# USB_SPI_I2C.net
KiCad netlist of a schematic drawn in Altium Designer
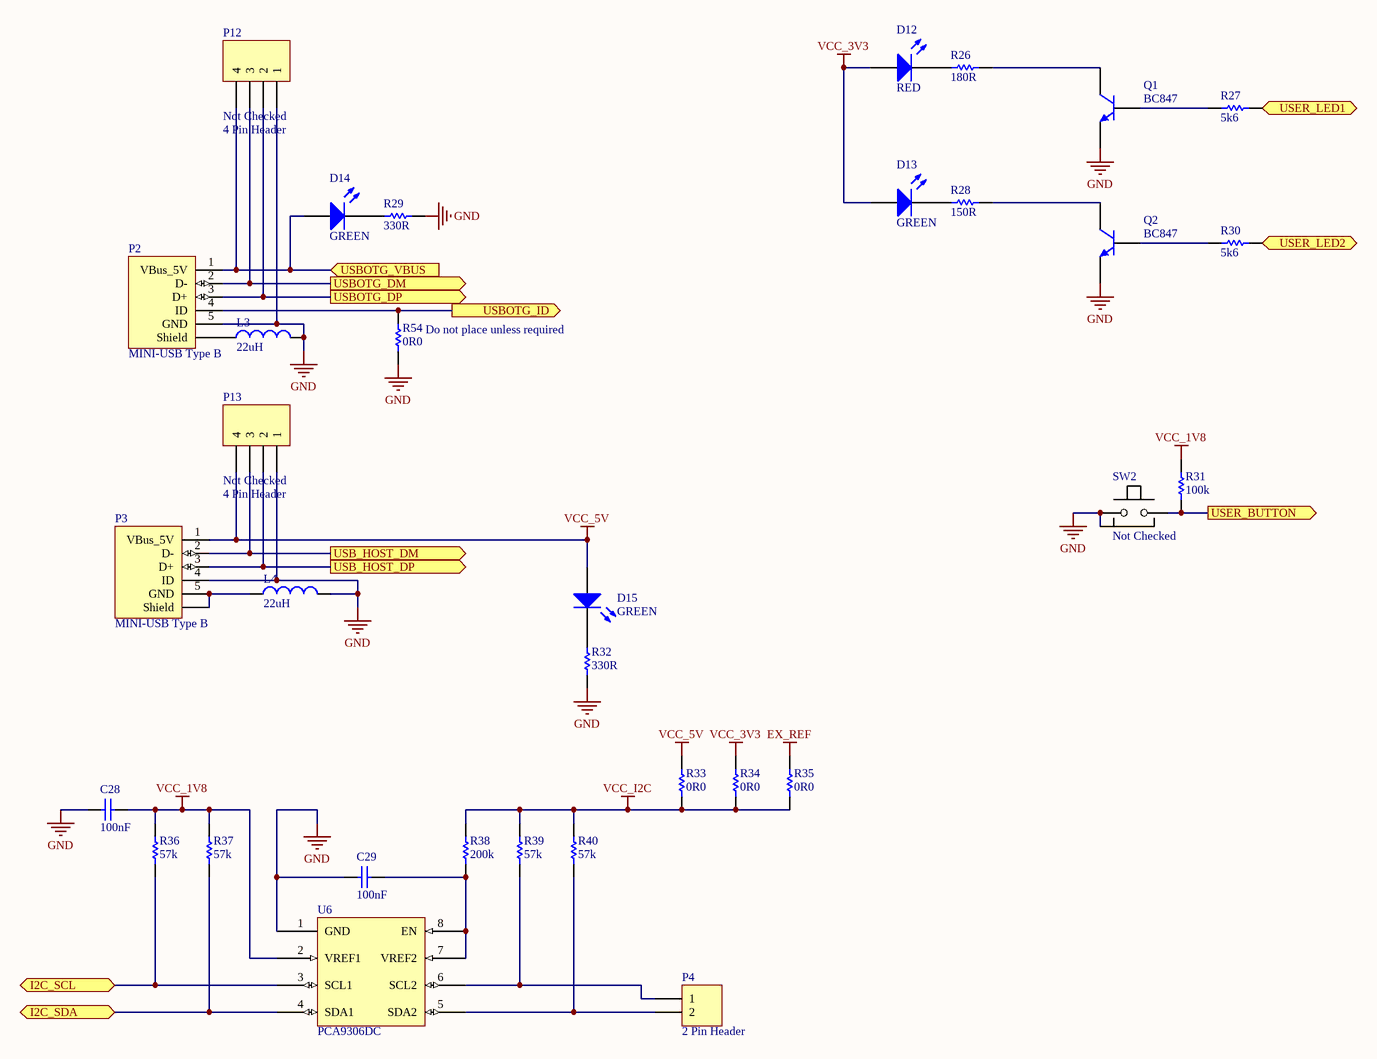
[diagram p0: USB SPI I2C.SchDoc]

(export (version "E")
  (design (tool "Eeschema 10.0.6"))
  (components
    (comp (ref "C28")
      (value "100nF")
      (footprint "GRC PCB library:0603")
      (description "CAP CER .10UF 50V X5R 0603")
      (fields (field (name "MANUFACTURER") "Taiyo Yuden"))
      (libsource (lib "GRC sch library") (part "CP_100nF 0603"))
    )
    (comp (ref "C29")
      (value "100nF")
      (footprint "GRC PCB library:0603")
      (description "CAP CER .10UF 50V X5R 0603")
      (fields (field (name "MANUFACTURER") "Taiyo Yuden"))
      (libsource (lib "GRC sch library") (part "CP_100nF 0603"))
    )
    (comp (ref "D12")
      (value "RED")
      (footprint "Diode_0805")
      (description "Red LED 0805")
      (fields (field (name "MANUFACTURER") "Vishay") (field (name "Comment") "LED Red"))
      (libsource (lib "GRC sch library") (part "DL_LED Red 0805"))
    )
    (comp (ref "D13")
      (value "GREEN")
      (footprint "Diode_0805")
      (description "Green LED 0805")
      (fields (field (name "Comment") "LED Green"))
      (libsource (lib "GRC sch library") (part "DL_LED Green 0805"))
    )
    (comp (ref "D14")
      (value "GREEN")
      (footprint "Diode_0805")
      (description "Green LED 0805")
      (fields (field (name "Comment") "LED Green"))
      (libsource (lib "GRC sch library") (part "DL_LED Green 0805"))
    )
    (comp (ref "D15")
      (value "GREEN")
      (footprint "Diode_0805")
      (description "Green LED 0805")
      (fields (field (name "Comment") "LED Green"))
      (libsource (lib "GRC sch library") (part "DL_LED Green 0805"))
    )
    (comp (ref "L3")
      (value "22uH")
      (footprint "GRC PCB library:0805")
      (description "Inductor 22uH 100mA 10% 0805")
      (fields (field (name "MANUFACTURER") "TDK Corporation"))
      (libsource (lib "GRC sch library") (part "IN_22uH 100mA 0805"))
    )
    (comp (ref "L4")
      (value "22uH")
      (footprint "GRC PCB library:0805")
      (description "Inductor 22uH 100mA 10% 0805")
      (fields (field (name "MANUFACTURER") "TDK Corporation"))
      (libsource (lib "GRC sch library") (part "IN_22uH 100mA 0805"))
    )
    (comp (ref "P2")
      (value "MINI-USB Type B")
      (footprint "Hir_MINI_USB_B")
      (description "MINI-USB Type B Single Connector")
      (fields (field (name "MANUFACTURER") "Hirose Electric Co Ltd"))
      (libsource (lib "GRC sch library") (part "JP_MINIUSB type B_1"))
    )
    (comp (ref "P3")
      (value "MINI-USB Type B")
      (footprint "Hir_MINI_USB_B")
      (description "MINI-USB Type B Single Connector")
      (fields (field (name "MANUFACTURER") "Hirose Electric Co Ltd"))
      (libsource (lib "GRC sch library") (part "JP_MINIUSB type B_1"))
    )
    (comp (ref "P4")
      (value "2 Pin Header")
      (footprint "CONN_2X1_SMT_RA_1.25MM")
      (description "CONN HDR VERT 2POS .100\" SNGL")
      (libsource (lib "checked") (part "JP_2PIN HDR_SMT_RA_MOLEX"))
    )
    (comp (ref "P12")
      (value "4 Pin Header")
      (footprint "CONN_4X1_SMT_RA_1.25MM")
      (description "CONN HDR VERT 4POS .100\" SNGL")
      (fields (field (name "MANUFACTURER") "Molex") (field (name "VERIFY") "Not Checked"))
      (libsource (lib "checked") (part "JP_4PIN HDR_SMT_RA_MOLEX"))
    )
    (comp (ref "P13")
      (value "4 Pin Header")
      (footprint "CONN_4X1_SMT_RA_1.25MM")
      (description "CONN HDR VERT 4POS .100\" SNGL")
      (fields (field (name "MANUFACTURER") "Molex") (field (name "VERIFY") "Not Checked"))
      (libsource (lib "checked") (part "JP_4PIN HDR_SMT_RA_MOLEX"))
    )
    (comp (ref "Q1")
      (value "BC847")
      (footprint "GRC PCB library:SOT23")
      (description "TRANS NPN GP 100MA 45V SOT23")
      (fields (field (name "MANUFACTURER") "NXP Semiconductors"))
      (libsource (lib "GRC sch library") (part "TN_BC847"))
    )
    (comp (ref "Q2")
      (value "BC847")
      (footprint "GRC PCB library:SOT23")
      (description "TRANS NPN GP 100MA 45V SOT23")
      (fields (field (name "MANUFACTURER") "NXP Semiconductors"))
      (libsource (lib "GRC sch library") (part "TN_BC847"))
    )
    (comp (ref "R26")
      (value "180R")
      (footprint "GRC PCB library:0603")
      (description "RES 180OHM 1/10W 1% 0603 SMD")
      (fields (field (name "MANUFACTURER") "Panasonic - ECG"))
      (libsource (lib "GRC sch library") (part "RS_180R 0603"))
    )
    (comp (ref "R27")
      (value "5k6")
      (footprint "GRC PCB library:0603")
      (description "RES 5.6K OHM 1/10W 5% 0603 SMD")
      (fields (field (name "MANUFACTURER") "Yageo"))
      (libsource (lib "GRC sch library") (part "RS_5k6 0603"))
    )
    (comp (ref "R28")
      (value "150R")
      (footprint "GRC PCB library:0603")
      (description "RES 150 OHM 1/10W 1% 0603 SMD")
      (fields (field (name "MANUFACTURER") "ROHM"))
      (libsource (lib "GRC sch library") (part "RS_150R 0603"))
    )
    (comp (ref "R29")
      (value "330R")
      (footprint "GRC PCB library:0603")
      (description "RES 330 OHM 1/10W 1% 0603 SMD")
      (fields (field (name "MANUFACTURER") "Yageo"))
      (libsource (lib "GRC sch library") (part "RS_330R 0603"))
    )
    (comp (ref "R30")
      (value "5k6")
      (footprint "GRC PCB library:0603")
      (description "RES 5.6K OHM 1/10W 5% 0603 SMD")
      (fields (field (name "MANUFACTURER") "Yageo"))
      (libsource (lib "GRC sch library") (part "RS_5k6 0603"))
    )
    (comp (ref "R31")
      (value "100k")
      (footprint "GRC PCB library:0603")
      (description "RES 100K OHM 1/10W 1% 0603 SMD")
      (fields (field (name "MANUFACTURER") "Yageo"))
      (libsource (lib "GRC sch library") (part "RS_100k 0603"))
    )
    (comp (ref "R32")
      (value "330R")
      (footprint "GRC PCB library:0603")
      (description "RES 100K OHM 1/10W 1% 0603 SMD")
      (fields (field (name "MANUFACTURER") "Yageo"))
      (libsource (lib "GRC sch library") (part "RS_100k 0603"))
    )
    (comp (ref "R33")
      (value "0R0")
      (footprint "GRC PCB library:0603")
      (description "RES 0.0 OHM 1/10W 5% 0603 SMD")
      (fields (field (name "MANUFACTURER") "Rohm"))
      (libsource (lib "GRC sch library") (part "RS_0R0 0603"))
    )
    (comp (ref "R34")
      (value "0R0")
      (footprint "GRC PCB library:0603")
      (description "RES 0.0 OHM 1/10W 5% 0603 SMD")
      (fields (field (name "MANUFACTURER") "Rohm"))
      (libsource (lib "GRC sch library") (part "RS_0R0 0603"))
    )
    (comp (ref "R35")
      (value "0R0")
      (footprint "GRC PCB library:0603")
      (description "RES 0.0 OHM 1/10W 5% 0603 SMD")
      (fields (field (name "MANUFACTURER") "Rohm"))
      (libsource (lib "GRC sch library") (part "RS_0R0 0603"))
    )
    (comp (ref "R36")
      (value "57k")
      (footprint "GRC PCB library:0603")
      (description "RES 10.0K OHM 1/10W 1% 0603 SMD")
      (fields (field (name "MANUFACTURER") "Yageo"))
      (libsource (lib "GRC sch library") (part "RS_10k 0603_1"))
    )
    (comp (ref "R37")
      (value "57k")
      (footprint "GRC PCB library:0603")
      (description "RES 10.0K OHM 1/10W 1% 0603 SMD")
      (fields (field (name "MANUFACTURER") "Yageo"))
      (libsource (lib "GRC sch library") (part "RS_10k 0603_1"))
    )
    (comp (ref "R38")
      (value "200k")
      (footprint "GRC PCB library:0603")
      (description "RES 10.0K OHM 1/10W 1% 0603 SMD")
      (fields (field (name "MANUFACTURER") "Yageo"))
      (libsource (lib "GRC sch library") (part "RS_10k 0603_1"))
    )
    (comp (ref "R39")
      (value "57k")
      (footprint "GRC PCB library:0603")
      (description "RES 10.0K OHM 1/10W 1% 0603 SMD")
      (fields (field (name "MANUFACTURER") "Yageo"))
      (libsource (lib "GRC sch library") (part "RS_10k 0603_1"))
    )
    (comp (ref "R40")
      (value "57k")
      (footprint "GRC PCB library:0603")
      (description "RES 10.0K OHM 1/10W 1% 0603 SMD")
      (fields (field (name "MANUFACTURER") "Yageo"))
      (libsource (lib "GRC sch library") (part "RS_10k 0603_1"))
    )
    (comp (ref "R54")
      (value "0R0")
      (footprint "GRC PCB library:0603")
      (description "RES 0.0 OHM 1/10W 5% 0603 SMD")
      (fields (field (name "MANUFACTURER") "Rohm"))
      (libsource (lib "GRC sch library") (part "RS_0R0 0603"))
    )
    (comp (ref "SW2")
      (value "Push Button Switch")
      (footprint "PUSHBUTTON_B3U")
      (description "SWITCH TACT RT ANG SPST SMD")
      (fields (field (name "MANUFACTURER") "Omron") (field (name "VERIFY") "Not Checked"))
      (libsource (lib "GRC sch library") (part "SW_TACT 3MM RT"))
    )
    (comp (ref "U6")
      (value "PCA9306DC")
      (footprint "VSSOP-8")
      (description "IC LEVEL TRANSLATOR I2C BUS 8VSSOP")
      (fields (field (name "MANUFACTURER") "NXP Semiconductor"))
      (libsource (lib "GRC sch library") (part "IC_PCA9306DC"))
    )
  )
  (nets
    (net (code "1") (name "/I2C_SCL") (class "Default")
      (node (ref "R36") (pin "1") (pinfunction "1_1") (pintype "passive"))
      (node (ref "U6") (pin "3") (pinfunction "SCL1_3") (pintype "bidirectional"))
    )
    (net (code "2") (name "/I2C_SDA") (class "Default")
      (node (ref "R37") (pin "1") (pinfunction "1_1") (pintype "passive"))
      (node (ref "U6") (pin "4") (pinfunction "SDA1_4") (pintype "bidirectional"))
    )
    (net (code "3") (name "/USBOTG_DM") (class "Default")
      (node (ref "P12") (pin "3") (pinfunction "3_3") (pintype "passive"))
      (node (ref "P2") (pin "2") (pinfunction "D-_2") (pintype "bidirectional"))
    )
    (net (code "4") (name "/USBOTG_DP") (class "Default")
      (node (ref "P12") (pin "2") (pinfunction "2_2") (pintype "passive"))
      (node (ref "P2") (pin "3") (pinfunction "D+_3") (pintype "bidirectional"))
    )
    (net (code "5") (name "/USBOTG_ID") (class "Default")
      (node (ref "P2") (pin "4") (pinfunction "ID_4") (pintype "passive"))
      (node (ref "R54") (pin "1") (pinfunction "1_1") (pintype "passive"))
    )
    (net (code "6") (name "/USBOTG_VBUS") (class "Default")
      (node (ref "D14") (pin "1") (pinfunction "A_1") (pintype "passive"))
      (node (ref "P12") (pin "4") (pinfunction "4_4") (pintype "passive"))
      (node (ref "P2") (pin "1") (pinfunction "VBus_5V_1") (pintype "passive"))
    )
    (net (code "7") (name "/USB_HOST_DM") (class "Default")
      (node (ref "P13") (pin "3") (pinfunction "3_3") (pintype "passive"))
      (node (ref "P3") (pin "2") (pinfunction "D-_2") (pintype "bidirectional"))
    )
    (net (code "8") (name "/USB_HOST_DP") (class "Default")
      (node (ref "P13") (pin "2") (pinfunction "2_2") (pintype "passive"))
      (node (ref "P3") (pin "3") (pinfunction "D+_3") (pintype "bidirectional"))
    )
    (net (code "9") (name "/USER_BUTTON") (class "Default")
      (node (ref "R31") (pin "2") (pinfunction "2_2") (pintype "passive"))
      (node (ref "SW2") (pin "2") (pinfunction "2_2") (pintype "passive"))
    )
    (net (code "10") (name "/USER_LED1") (class "Default")
      (node (ref "R27") (pin "2") (pinfunction "2_2") (pintype "passive"))
    )
    (net (code "11") (name "/USER_LED2") (class "Default")
      (node (ref "R30") (pin "2") (pinfunction "2_2") (pintype "passive"))
    )
    (net (code "12") (name "EX_REF") (class "Default")
      (node (ref "R35") (pin "1") (pinfunction "1_1") (pintype "passive"))
    )
    (net (code "13") (name "GND") (class "Default")
      (node (ref "C28") (pin "2") (pinfunction "2_2") (pintype "passive"))
      (node (ref "C29") (pin "2") (pinfunction "2_2") (pintype "passive"))
      (node (ref "L3") (pin "2") (pinfunction "2_2") (pintype "passive"))
      (node (ref "L4") (pin "2") (pinfunction "2_2") (pintype "passive"))
      (node (ref "P12") (pin "1") (pinfunction "1_1") (pintype "passive"))
      (node (ref "P13") (pin "1") (pinfunction "1_1") (pintype "passive"))
      (node (ref "P2") (pin "5") (pinfunction "GND_5") (pintype "passive"))
      (node (ref "P3") (pin "4") (pinfunction "ID_4") (pintype "passive"))
      (node (ref "Q1") (pin "2") (pinfunction "E_2") (pintype "passive"))
      (node (ref "Q2") (pin "2") (pinfunction "E_2") (pintype "passive"))
      (node (ref "R29") (pin "2") (pinfunction "2_2") (pintype "passive"))
      (node (ref "R32") (pin "1") (pinfunction "1_1") (pintype "passive"))
      (node (ref "R54") (pin "2") (pinfunction "2_2") (pintype "passive"))
      (node (ref "SW2") (pin "1") (pinfunction "1_1") (pintype "passive"))
      (node (ref "SW2") (pin "3") (pinfunction "GND_3") (pintype "passive"))
      (node (ref "U6") (pin "1") (pinfunction "GND_1") (pintype "power_in"))
    )
    (net (code "14") (name "Net-(D12-K)") (class "Default")
      (node (ref "D12") (pin "2") (pinfunction "K_2") (pintype "passive"))
      (node (ref "R26") (pin "1") (pinfunction "1_1") (pintype "passive"))
    )
    (net (code "15") (name "Net-(D13-K)") (class "Default")
      (node (ref "D13") (pin "2") (pinfunction "K_2") (pintype "passive"))
      (node (ref "R28") (pin "1") (pinfunction "1_1") (pintype "passive"))
    )
    (net (code "16") (name "Net-(D14-K)") (class "Default")
      (node (ref "D14") (pin "2") (pinfunction "K_2") (pintype "passive"))
      (node (ref "R29") (pin "1") (pinfunction "1_1") (pintype "passive"))
    )
    (net (code "17") (name "Net-(D15-K)") (class "Default")
      (node (ref "D15") (pin "2") (pinfunction "K_2") (pintype "passive"))
      (node (ref "R32") (pin "2") (pinfunction "2_2") (pintype "passive"))
    )
    (net (code "18") (name "Net-(P2-Shield)") (class "Default")
      (node (ref "L3") (pin "1") (pinfunction "1_1") (pintype "passive"))
      (node (ref "P2") (pin "6") (pinfunction "Shield_6") (pintype "passive"))
    )
    (net (code "19") (name "Net-(P3-GND)") (class "Default")
      (node (ref "L4") (pin "1") (pinfunction "1_1") (pintype "passive"))
      (node (ref "P3") (pin "5") (pinfunction "GND_5") (pintype "passive"))
      (node (ref "P3") (pin "6") (pinfunction "Shield_6") (pintype "passive"))
    )
    (net (code "20") (name "Net-(Q1-B)") (class "Default")
      (node (ref "Q1") (pin "1") (pinfunction "B_1") (pintype "passive"))
      (node (ref "R27") (pin "1") (pinfunction "1_1") (pintype "passive"))
    )
    (net (code "21") (name "Net-(Q1-C)") (class "Default")
      (node (ref "Q1") (pin "3") (pinfunction "C_3") (pintype "passive"))
      (node (ref "R26") (pin "2") (pinfunction "2_2") (pintype "passive"))
    )
    (net (code "22") (name "Net-(Q2-B)") (class "Default")
      (node (ref "Q2") (pin "1") (pinfunction "B_1") (pintype "passive"))
      (node (ref "R30") (pin "1") (pinfunction "1_1") (pintype "passive"))
    )
    (net (code "23") (name "Net-(Q2-C)") (class "Default")
      (node (ref "Q2") (pin "3") (pinfunction "C_3") (pintype "passive"))
      (node (ref "R28") (pin "2") (pinfunction "2_2") (pintype "passive"))
    )
    (net (code "24") (name "Net-(U6-EN)") (class "Default")
      (node (ref "C29") (pin "1") (pinfunction "1_1") (pintype "passive"))
      (node (ref "R38") (pin "1") (pinfunction "1_1") (pintype "passive"))
      (node (ref "U6") (pin "7") (pinfunction "VREF2_7") (pintype "input"))
      (node (ref "U6") (pin "8") (pinfunction "EN_8") (pintype "input"))
    )
    (net (code "25") (name "Net-(U6-SCL2)") (class "Default")
      (node (ref "P4") (pin "1") (pinfunction "1_1") (pintype "passive"))
      (node (ref "R39") (pin "1") (pinfunction "1_1") (pintype "passive"))
      (node (ref "U6") (pin "6") (pinfunction "SCL2_6") (pintype "bidirectional"))
    )
    (net (code "26") (name "Net-(U6-SDA2)") (class "Default")
      (node (ref "P4") (pin "2") (pinfunction "2_2") (pintype "passive"))
      (node (ref "R40") (pin "1") (pinfunction "1_1") (pintype "passive"))
      (node (ref "U6") (pin "5") (pinfunction "SDA2_5") (pintype "bidirectional"))
    )
    (net (code "27") (name "VCC_1V8") (class "Default")
      (node (ref "C28") (pin "1") (pinfunction "1_1") (pintype "passive"))
      (node (ref "R31") (pin "1") (pinfunction "1_1") (pintype "passive"))
      (node (ref "R36") (pin "2") (pinfunction "2_2") (pintype "passive"))
      (node (ref "R37") (pin "2") (pinfunction "2_2") (pintype "passive"))
      (node (ref "U6") (pin "2") (pinfunction "VREF1_2") (pintype "input"))
    )
    (net (code "28") (name "VCC_3V3") (class "Default")
      (node (ref "D12") (pin "1") (pinfunction "A_1") (pintype "passive"))
      (node (ref "D13") (pin "1") (pinfunction "A_1") (pintype "passive"))
      (node (ref "R34") (pin "1") (pinfunction "1_1") (pintype "passive"))
    )
    (net (code "29") (name "VCC_5V") (class "Default")
      (node (ref "D15") (pin "1") (pinfunction "A_1") (pintype "passive"))
      (node (ref "P13") (pin "4") (pinfunction "4_4") (pintype "passive"))
      (node (ref "P3") (pin "1") (pinfunction "VBus_5V_1") (pintype "passive"))
      (node (ref "R33") (pin "1") (pinfunction "1_1") (pintype "passive"))
    )
    (net (code "30") (name "VCC_I2C") (class "Default")
      (node (ref "R33") (pin "2") (pinfunction "2_2") (pintype "passive"))
      (node (ref "R34") (pin "2") (pinfunction "2_2") (pintype "passive"))
      (node (ref "R35") (pin "2") (pinfunction "2_2") (pintype "passive"))
      (node (ref "R38") (pin "2") (pinfunction "2_2") (pintype "passive"))
      (node (ref "R39") (pin "2") (pinfunction "2_2") (pintype "passive"))
      (node (ref "R40") (pin "2") (pinfunction "2_2") (pintype "passive"))
    )
  )
)
